# MotorDrivers.net
KiCad netlist of a schematic drawn in Altium Designer
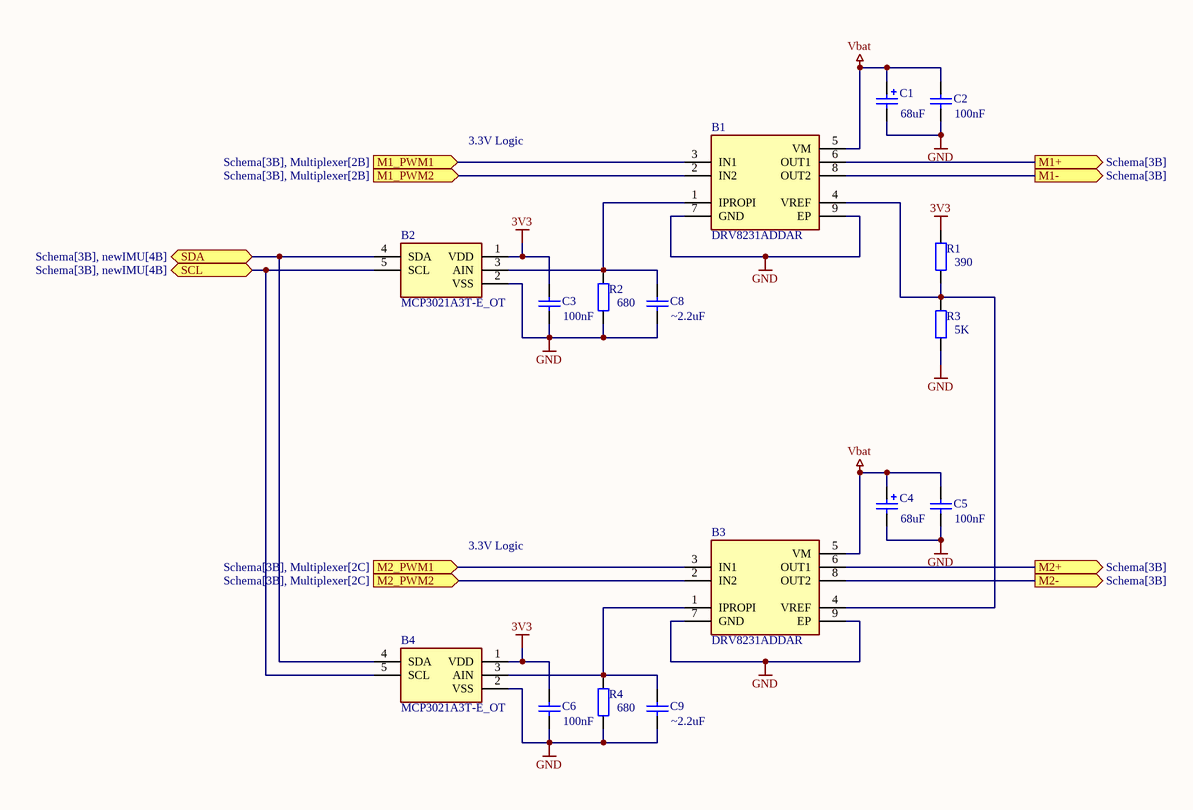
[diagram p0: MotorDrivers.SchDoc]

(export (version "E")
  (design (tool "Eeschema 10.0.6"))
  (components
    (comp (ref "B1")
      (value "DRV8231ADDAR")
      (footprint "SOIC127P600X170-9M")
      (description "Motor Drives 33V H bridge motor driver with current regulation and current sense feedback")
      (fields (field (name "MOUSER PART NUMBER") "595-DRV8231ADDAR"))
      (libsource (lib "SchematicLib") (part "DRV8231ADDAR"))
    )
    (comp (ref "B2")
      (value "MCP3021A3T-E_OT")
      (footprint "SOT95P280X145-5M")
      (description "Analog to Digital Converters - ADC 10-bit ADC I2C Single Channel")
      (fields
        (field (name "MOUSER PART NUMBER") "579-MCP3021A3T-E/OT")
        (field (name "MANUFACTURER_PART_NUMBER") "MCP3021A3T-E/OT")
      )
      (libsource (lib "SchematicLib") (part "MCP3021A3T-E_OT"))
    )
    (comp (ref "B3")
      (value "DRV8231ADDAR")
      (footprint "SOIC127P600X170-9M")
      (description "Motor Drives 33V H bridge motor driver with current regulation and current sense feedback")
      (fields (field (name "MOUSER PART NUMBER") "595-DRV8231ADDAR"))
      (libsource (lib "SchematicLib") (part "DRV8231ADDAR"))
    )
    (comp (ref "B4")
      (value "MCP3021A3T-E_OT")
      (footprint "SOT95P280X145-5M")
      (description "Analog to Digital Converters - ADC 10-bit ADC I2C Single Channel")
      (fields
        (field (name "MOUSER PART NUMBER") "579-MCP3021A3T-E/OT")
        (field (name "MANUFACTURER_PART_NUMBER") "MCP3021A3T-E/OT")
      )
      (libsource (lib "SchematicLib") (part "MCP3021A3T-E_OT"))
    )
    (comp (ref "C1")
      (value "68uF")
      (footprint "CAP68uF")
      (description "Polarized Capacitor (Axial)")
      (fields (field (name "Comment") "Cap Pol2") (field (name "PUBLISHER") "Altium Limited"))
      (libsource (lib "Miscellaneous Devices") (part "Cap Pol2"))
    )
    (comp (ref "C2")
      (value "100nF")
      (footprint "0805_Lorin")
      (description "Capacitor")
      (fields (field (name "Comment") "Cap") (field (name "PUBLISHER") "Altium Limited"))
      (libsource (lib "Miscellaneous Devices") (part "Cap"))
    )
    (comp (ref "C3")
      (value "100nF")
      (footprint "0805_Lorin")
      (description "Capacitor")
      (fields (field (name "Comment") "Cap") (field (name "PUBLISHER") "Altium Limited"))
      (libsource (lib "Miscellaneous Devices") (part "Cap"))
    )
    (comp (ref "C4")
      (value "68uF")
      (footprint "CAP68uF")
      (description "Polarized Capacitor (Axial)")
      (fields (field (name "Comment") "Cap Pol2") (field (name "PUBLISHER") "Altium Limited"))
      (libsource (lib "Miscellaneous Devices") (part "Cap Pol2"))
    )
    (comp (ref "C5")
      (value "100nF")
      (footprint "0805_Lorin")
      (description "Capacitor")
      (fields (field (name "Comment") "Cap") (field (name "PUBLISHER") "Altium Limited"))
      (libsource (lib "Miscellaneous Devices") (part "Cap"))
    )
    (comp (ref "C6")
      (value "100nF")
      (footprint "0805_Lorin")
      (description "Capacitor")
      (fields (field (name "Comment") "Cap") (field (name "PUBLISHER") "Altium Limited"))
      (libsource (lib "Miscellaneous Devices") (part "Cap"))
    )
    (comp (ref "C8")
      (value "~2.2uF")
      (footprint "0805_Lorin")
      (description "Capacitor")
      (fields (field (name "Comment") "Cap") (field (name "PUBLISHER") "Altium Limited"))
      (libsource (lib "Miscellaneous Devices") (part "Cap"))
    )
    (comp (ref "C9")
      (value "~2.2uF")
      (footprint "0805_Lorin")
      (description "Capacitor")
      (fields (field (name "Comment") "Cap") (field (name "PUBLISHER") "Altium Limited"))
      (libsource (lib "Miscellaneous Devices") (part "Cap"))
    )
    (comp (ref "R1")
      (value "390")
      (footprint "0805_Lorin")
      (description "Resistor")
      (fields (field (name "Comment") "Res2") (field (name "PUBLISHER") "Altium Limited"))
      (libsource (lib "Miscellaneous Devices") (part "Res2"))
    )
    (comp (ref "R2")
      (value "680")
      (footprint "0805_Lorin")
      (description "Resistor")
      (fields (field (name "Comment") "Res2") (field (name "PUBLISHER") "Altium Limited"))
      (libsource (lib "Miscellaneous Devices") (part "Res2"))
    )
    (comp (ref "R3")
      (value "5K")
      (footprint "0805_Lorin")
      (description "Resistor")
      (fields (field (name "Comment") "Res2") (field (name "PUBLISHER") "Altium Limited"))
      (libsource (lib "Miscellaneous Devices") (part "Res2"))
    )
    (comp (ref "R4")
      (value "680")
      (footprint "0805_Lorin")
      (description "Resistor")
      (fields (field (name "Comment") "Res2") (field (name "PUBLISHER") "Altium Limited"))
      (libsource (lib "Miscellaneous Devices") (part "Res2"))
    )
  )
  (nets
    (net (code "1") (name "/M1+") (class "Default")
      (node (ref "B1") (pin "6") (pinfunction "OUT1_6") (pintype "passive"))
    )
    (net (code "2") (name "/M1-") (class "Default")
      (node (ref "B1") (pin "8") (pinfunction "OUT2_8") (pintype "passive"))
    )
    (net (code "3") (name "/M1_PWM1") (class "Default")
      (node (ref "B1") (pin "3") (pinfunction "IN1_3") (pintype "passive"))
    )
    (net (code "4") (name "/M1_PWM2") (class "Default")
      (node (ref "B1") (pin "2") (pinfunction "IN2_2") (pintype "passive"))
    )
    (net (code "5") (name "/M2+") (class "Default")
      (node (ref "B3") (pin "6") (pinfunction "OUT1_6") (pintype "passive"))
    )
    (net (code "6") (name "/M2-") (class "Default")
      (node (ref "B3") (pin "8") (pinfunction "OUT2_8") (pintype "passive"))
    )
    (net (code "7") (name "/M2_PWM1") (class "Default")
      (node (ref "B3") (pin "3") (pinfunction "IN1_3") (pintype "passive"))
    )
    (net (code "8") (name "/M2_PWM2") (class "Default")
      (node (ref "B3") (pin "2") (pinfunction "IN2_2") (pintype "passive"))
    )
    (net (code "9") (name "/SCL") (class "Default")
      (node (ref "B2") (pin "5") (pinfunction "SCL_5") (pintype "passive"))
      (node (ref "B4") (pin "5") (pinfunction "SCL_5") (pintype "passive"))
    )
    (net (code "10") (name "/SDA") (class "Default")
      (node (ref "B2") (pin "4") (pinfunction "SDA_4") (pintype "passive"))
      (node (ref "B4") (pin "4") (pinfunction "SDA_4") (pintype "passive"))
    )
    (net (code "11") (name "3V3") (class "Default")
      (node (ref "B2") (pin "1") (pinfunction "VDD_1") (pintype "passive"))
      (node (ref "B4") (pin "1") (pinfunction "VDD_1") (pintype "passive"))
      (node (ref "C3") (pin "2") (pinfunction "2_2") (pintype "passive"))
      (node (ref "C6") (pin "2") (pinfunction "2_2") (pintype "passive"))
      (node (ref "R1") (pin "2") (pinfunction "2_2") (pintype "passive"))
    )
    (net (code "12") (name "GND") (class "Default")
      (node (ref "B1") (pin "7") (pinfunction "GND_7") (pintype "passive"))
      (node (ref "B1") (pin "9") (pinfunction "EP_9") (pintype "passive"))
      (node (ref "B2") (pin "2") (pinfunction "VSS_2") (pintype "passive"))
      (node (ref "B3") (pin "7") (pinfunction "GND_7") (pintype "passive"))
      (node (ref "B3") (pin "9") (pinfunction "EP_9") (pintype "passive"))
      (node (ref "B4") (pin "2") (pinfunction "VSS_2") (pintype "passive"))
      (node (ref "C1") (pin "2") (pinfunction "2_2") (pintype "passive"))
      (node (ref "C2") (pin "2") (pinfunction "2_2") (pintype "passive"))
      (node (ref "C3") (pin "1") (pinfunction "1_1") (pintype "passive"))
      (node (ref "C4") (pin "2") (pinfunction "2_2") (pintype "passive"))
      (node (ref "C5") (pin "2") (pinfunction "2_2") (pintype "passive"))
      (node (ref "C6") (pin "1") (pinfunction "1_1") (pintype "passive"))
      (node (ref "C8") (pin "1") (pinfunction "1_1") (pintype "passive"))
      (node (ref "C9") (pin "1") (pinfunction "1_1") (pintype "passive"))
      (node (ref "R2") (pin "1") (pinfunction "1_1") (pintype "passive"))
      (node (ref "R3") (pin "1") (pinfunction "1_1") (pintype "passive"))
      (node (ref "R4") (pin "1") (pinfunction "1_1") (pintype "passive"))
    )
    (net (code "13") (name "Net-(B1-IPROPI)") (class "Default")
      (node (ref "B1") (pin "1") (pinfunction "IPROPI_1") (pintype "passive"))
      (node (ref "B2") (pin "3") (pinfunction "AIN_3") (pintype "passive"))
      (node (ref "C8") (pin "2") (pinfunction "2_2") (pintype "passive"))
      (node (ref "R2") (pin "2") (pinfunction "2_2") (pintype "passive"))
    )
    (net (code "14") (name "Net-(B1-VREF)") (class "Default")
      (node (ref "B1") (pin "4") (pinfunction "VREF_4") (pintype "passive"))
      (node (ref "B3") (pin "4") (pinfunction "VREF_4") (pintype "passive"))
      (node (ref "R1") (pin "1") (pinfunction "1_1") (pintype "passive"))
      (node (ref "R3") (pin "2") (pinfunction "2_2") (pintype "passive"))
    )
    (net (code "15") (name "Net-(B3-IPROPI)") (class "Default")
      (node (ref "B3") (pin "1") (pinfunction "IPROPI_1") (pintype "passive"))
      (node (ref "B4") (pin "3") (pinfunction "AIN_3") (pintype "passive"))
      (node (ref "C9") (pin "2") (pinfunction "2_2") (pintype "passive"))
      (node (ref "R4") (pin "2") (pinfunction "2_2") (pintype "passive"))
    )
    (net (code "16") (name "Vbat") (class "Default")
      (node (ref "B1") (pin "5") (pinfunction "VM_5") (pintype "passive"))
      (node (ref "B3") (pin "5") (pinfunction "VM_5") (pintype "passive"))
      (node (ref "C1") (pin "1") (pinfunction "1_1") (pintype "passive"))
      (node (ref "C2") (pin "1") (pinfunction "1_1") (pintype "passive"))
      (node (ref "C4") (pin "1") (pinfunction "1_1") (pintype "passive"))
      (node (ref "C5") (pin "1") (pinfunction "1_1") (pintype "passive"))
    )
  )
)
